# OZ440-SE100-CAR003_Sheet1.net
KiCad netlist of a schematic drawn in Altium Designer
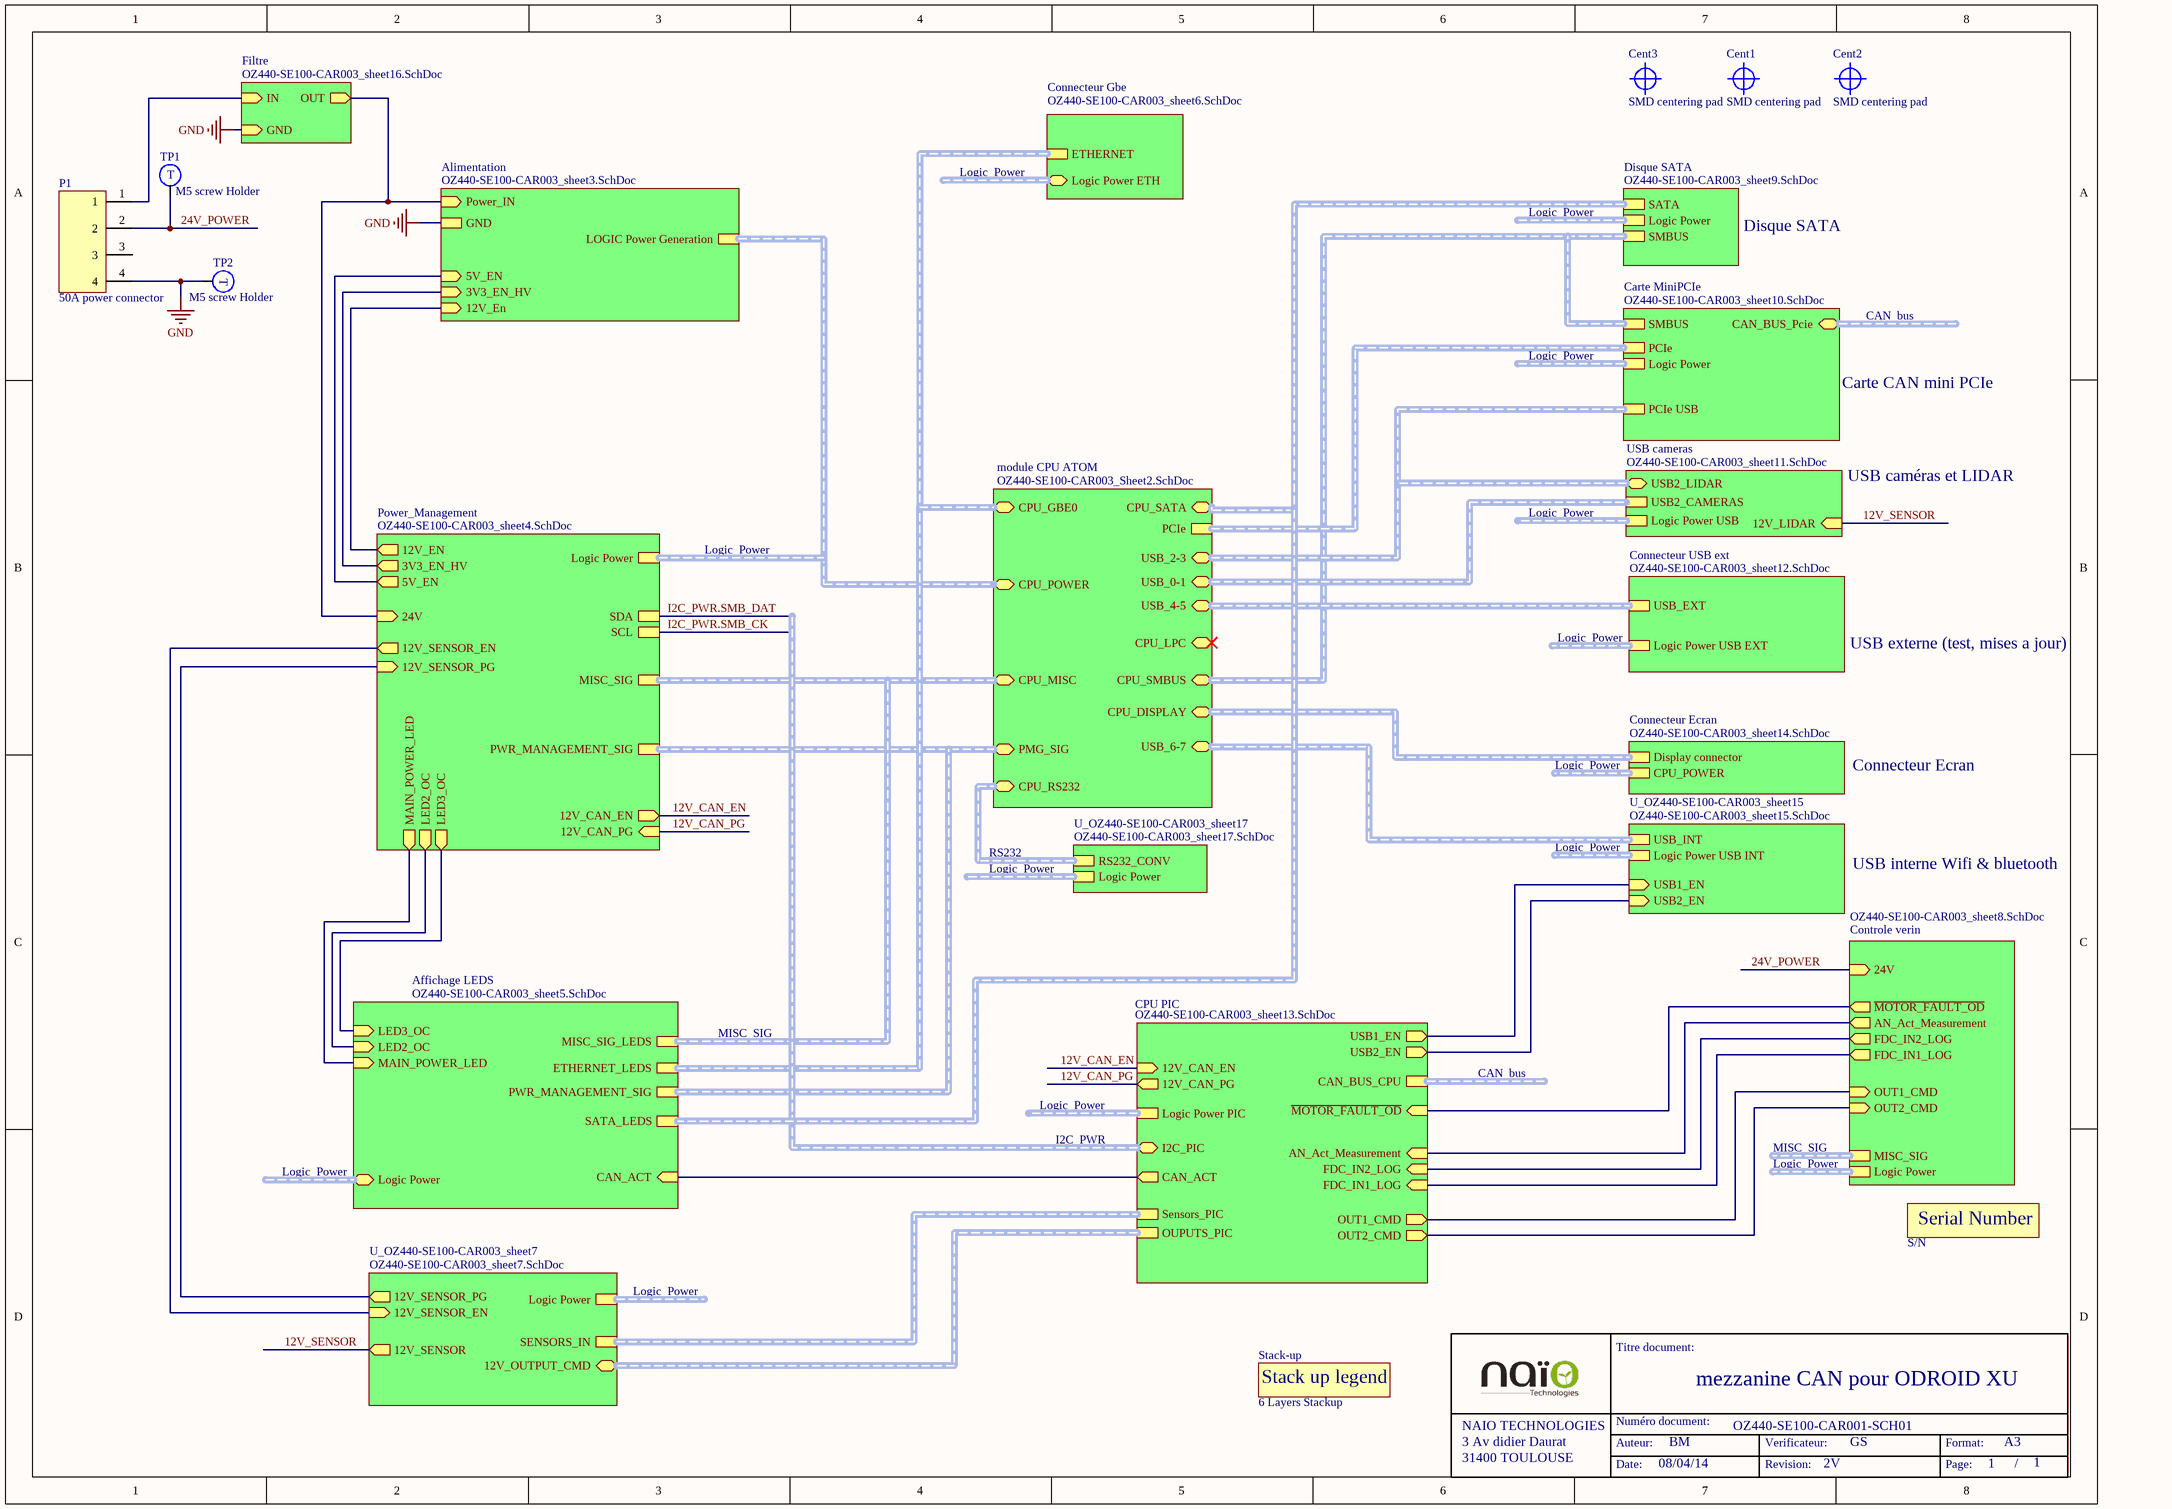
[diagram p0: OZ440-SE100-CAR003_Sheet1.SchDoc]

(export (version "E")
  (design (tool "Eeschema 10.0.6"))
  (components
    (comp (ref "Cent1")
      (value "MEC-STD-CENTER")
      (footprint "MEC-STD-CENTER")
      (description "SMD centering pad")
      (fields (field (name "DISPLAYED REFERENCE") "SMD centering pad"))
      (libsource (lib "lib_NAIO") (part "MEC-STD-CENTER"))
    )
    (comp (ref "Cent2")
      (value "MEC-STD-CENTER")
      (footprint "MEC-STD-CENTER")
      (description "SMD centering pad")
      (fields (field (name "DISPLAYED REFERENCE") "SMD centering pad"))
      (libsource (lib "lib_NAIO") (part "MEC-STD-CENTER"))
    )
    (comp (ref "Cent3")
      (value "MEC-STD-CENTER")
      (footprint "MEC-STD-CENTER")
      (description "SMD centering pad")
      (fields (field (name "DISPLAYED REFERENCE") "SMD centering pad"))
      (libsource (lib "lib_NAIO") (part "MEC-STD-CENTER"))
    )
    (comp (ref "P1")
      (value "CONN-STD-4P_puissance")
      (footprint "CONN-SPE-428204213_MOLEX")
      (description "4 pin power connector, RA")
      (fields
        (field (name "DISPLAYED REFERENCE") "50A power connector")
        (field (name "MANUFACTURER") "Molex")
      )
      (libsource (lib "lib_NAIO") (part "CONN-STD-4P_puissance"))
    )
    (comp (ref "SN1")
      (value "SERIAL-NUMBER")
      (footprint "SERIAL_NUMBER-STD")
      (description "serial number copper identification")
      (fields (field (name "DISPLAYED REFERENCE") "S/N"))
      (libsource (lib "lib_NAIO") (part "SERIAL-NUMBER"))
    )
    (comp (ref "Stack-up")
      (value "STACKUP")
      (footprint "STACKUP-SPE-6LAYERS")
      (description "6 Layers Stackup identification")
      (fields (field (name "DISPLAYED REFERENCE") "6 Layers Stackup"))
      (libsource (lib "lib_NAIO") (part "STACKUP"))
    )
    (comp (ref "TP1")
      (value "TP-STD-TEST_POINT")
      (footprint "MEC-SPE-WURTHZ_7460408")
      (description "Bush with threaded hole M5")
      (fields (field (name "DISPLAYED REFERENCE") "M5 screw Holder") (field (name "MANUFACTURER") "WURTHZ"))
      (libsource (lib "lib_NAIO") (part "TP-STD-TEST_POINT"))
    )
    (comp (ref "TP2")
      (value "TP-STD-TEST_POINT")
      (footprint "MEC-SPE-WURTHZ_7460408")
      (description "Bush with threaded hole M5")
      (fields (field (name "DISPLAYED REFERENCE") "M5 screw Holder") (field (name "MANUFACTURER") "WURTHZ"))
      (libsource (lib "lib_NAIO") (part "TP-STD-TEST_POINT"))
    )
  )
  (nets
    (net (code "15") (name "/24V_POWER") (class "Default")
      (node (ref "P1") (pin "2") (pinfunction "2_2") (pintype "passive"))
      (node (ref "TP1") (pin "1") (pinfunction "T_1") (pintype "passive"))
    )
    (net (code "29") (name "/IN") (class "Default")
      (node (ref "P1") (pin "1") (pinfunction "1_1") (pintype "passive"))
    )
    (net (code "55") (name "GND") (class "Default")
      (node (ref "P1") (pin "4") (pinfunction "4_4") (pintype "passive"))
      (node (ref "TP2") (pin "1") (pinfunction "T_1") (pintype "passive"))
    )
    (net (code "56") (name "unconnected-(P1-Pad3)") (class "Default")
      (node (ref "P1") (pin "3") (pinfunction "3_3") (pintype "passive"))
    )
  )
)
